# Inputs.net
KiCad netlist of a schematic drawn in Altium Designer
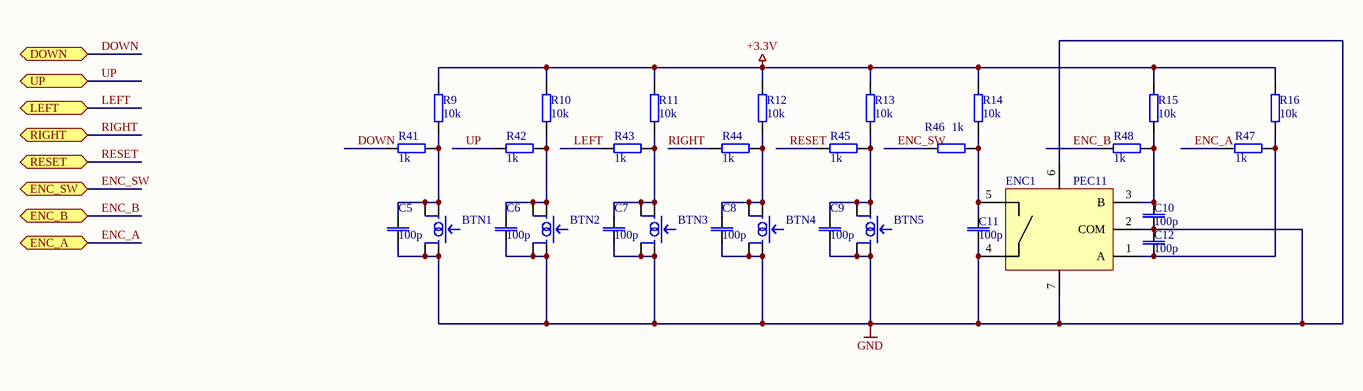
[diagram p0: Inputs.SchDoc]

(export (version "E")
  (design (tool "Eeschema 10.0.6"))
  (components
    (comp (ref "BTN1")
      (value "~")
      (footprint "PBUTTON_SMD")
      (description "Tactile push button")
      (libsource (lib "SCH_LIB") (part "PUSHBUTTON"))
    )
    (comp (ref "BTN2")
      (value "~")
      (footprint "PBUTTON_SMD")
      (description "Tactile push button")
      (libsource (lib "SCH_LIB") (part "PUSHBUTTON"))
    )
    (comp (ref "BTN3")
      (value "~")
      (footprint "PBUTTON_SMD")
      (description "Tactile push button")
      (libsource (lib "SCH_LIB") (part "PUSHBUTTON"))
    )
    (comp (ref "BTN4")
      (value "~")
      (footprint "PBUTTON_SMD")
      (description "Tactile push button")
      (libsource (lib "SCH_LIB") (part "PUSHBUTTON"))
    )
    (comp (ref "BTN5")
      (value "~")
      (footprint "PBUTTON_SMD")
      (description "Tactile push button")
      (libsource (lib "SCH_LIB") (part "PUSHBUTTON"))
    )
    (comp (ref "C5")
      (value "100p")
      (footprint "CAP 0805")
      (description "NON POLARIZED CAPACITOR")
      (libsource (lib "SCH_LIB") (part "CAP"))
    )
    (comp (ref "C6")
      (value "100p")
      (footprint "CAP 0805")
      (description "NON POLARIZED CAPACITOR")
      (libsource (lib "SCH_LIB") (part "CAP"))
    )
    (comp (ref "C7")
      (value "100p")
      (footprint "CAP 0805")
      (description "NON POLARIZED CAPACITOR")
      (libsource (lib "SCH_LIB") (part "CAP"))
    )
    (comp (ref "C8")
      (value "100p")
      (footprint "CAP 0805")
      (description "NON POLARIZED CAPACITOR")
      (libsource (lib "SCH_LIB") (part "CAP"))
    )
    (comp (ref "C9")
      (value "100p")
      (footprint "CAP 0805")
      (description "NON POLARIZED CAPACITOR")
      (libsource (lib "SCH_LIB") (part "CAP"))
    )
    (comp (ref "C10")
      (value "100p")
      (footprint "CAP 0805")
      (description "NON POLARIZED CAPACITOR")
      (libsource (lib "SCH_LIB") (part "CAP"))
    )
    (comp (ref "C11")
      (value "100p")
      (footprint "CAP 0805")
      (description "NON POLARIZED CAPACITOR")
      (libsource (lib "SCH_LIB") (part "CAP"))
    )
    (comp (ref "C12")
      (value "100p")
      (footprint "CAP 0805")
      (description "NON POLARIZED CAPACITOR")
      (libsource (lib "SCH_LIB") (part "CAP"))
    )
    (comp (ref "ENC1")
      (value "PEC11")
      (footprint "PEC11")
      (description "Mechanical rotary encoder with pushbutton")
      (libsource (lib "SCH_LIB") (part "PEC11"))
    )
    (comp (ref "R9")
      (value "10k")
      (footprint "RES 0805")
      (description "RESISTOR")
      (libsource (lib "") (part "RES_1"))
    )
    (comp (ref "R10")
      (value "10k")
      (footprint "RES 0805")
      (description "RESISTOR")
      (libsource (lib "") (part "RES_1"))
    )
    (comp (ref "R11")
      (value "10k")
      (footprint "RES 0805")
      (description "RESISTOR")
      (libsource (lib "") (part "RES_1"))
    )
    (comp (ref "R12")
      (value "10k")
      (footprint "RES 0805")
      (description "RESISTOR")
      (libsource (lib "") (part "RES_1"))
    )
    (comp (ref "R13")
      (value "10k")
      (footprint "RES 0805")
      (description "RESISTOR")
      (libsource (lib "") (part "RES_1"))
    )
    (comp (ref "R14")
      (value "10k")
      (footprint "RES 0805")
      (description "RESISTOR")
      (libsource (lib "") (part "RES_1"))
    )
    (comp (ref "R15")
      (value "10k")
      (footprint "RES 0805")
      (description "RESISTOR")
      (libsource (lib "") (part "RES_1"))
    )
    (comp (ref "R16")
      (value "10k")
      (footprint "RES 0805")
      (description "RESISTOR")
      (libsource (lib "") (part "RES_1"))
    )
    (comp (ref "R41")
      (value "1k")
      (footprint "RES 0805")
      (description "RESISTOR")
      (libsource (lib "SCH_LIB") (part "RES"))
    )
    (comp (ref "R42")
      (value "1k")
      (footprint "RES 0805")
      (description "RESISTOR")
      (libsource (lib "SCH_LIB") (part "RES"))
    )
    (comp (ref "R43")
      (value "1k")
      (footprint "RES 0805")
      (description "RESISTOR")
      (libsource (lib "SCH_LIB") (part "RES"))
    )
    (comp (ref "R44")
      (value "1k")
      (footprint "RES 0805")
      (description "RESISTOR")
      (libsource (lib "SCH_LIB") (part "RES"))
    )
    (comp (ref "R45")
      (value "1k")
      (footprint "RES 0805")
      (description "RESISTOR")
      (libsource (lib "SCH_LIB") (part "RES"))
    )
    (comp (ref "R46")
      (value "1k")
      (footprint "RES 0805")
      (description "RESISTOR")
      (libsource (lib "SCH_LIB") (part "RES"))
    )
    (comp (ref "R47")
      (value "1k")
      (footprint "RES 0805")
      (description "RESISTOR")
      (libsource (lib "SCH_LIB") (part "RES"))
    )
    (comp (ref "R48")
      (value "1k")
      (footprint "RES 0805")
      (description "RESISTOR")
      (libsource (lib "SCH_LIB") (part "RES"))
    )
  )
  (nets
    (net (code "1") (name "+3.3V") (class "Default")
      (node (ref "R10") (pin "2") (pinfunction "2_2") (pintype "passive"))
      (node (ref "R11") (pin "2") (pinfunction "2_2") (pintype "passive"))
      (node (ref "R12") (pin "2") (pinfunction "2_2") (pintype "passive"))
      (node (ref "R13") (pin "2") (pinfunction "2_2") (pintype "passive"))
      (node (ref "R14") (pin "2") (pinfunction "2_2") (pintype "passive"))
      (node (ref "R15") (pin "2") (pinfunction "2_2") (pintype "passive"))
      (node (ref "R16") (pin "2") (pinfunction "2_2") (pintype "passive"))
      (node (ref "R9") (pin "2") (pinfunction "2_2") (pintype "passive"))
    )
    (net (code "2") (name "/DOWN") (class "Default")
      (node (ref "R41") (pin "1") (pinfunction "1_1") (pintype "passive"))
    )
    (net (code "3") (name "/ENC_A") (class "Default")
      (node (ref "R47") (pin "1") (pinfunction "1_1") (pintype "passive"))
    )
    (net (code "4") (name "/ENC_B") (class "Default")
      (node (ref "R48") (pin "1") (pinfunction "1_1") (pintype "passive"))
    )
    (net (code "5") (name "/ENC_SW") (class "Default")
      (node (ref "R46") (pin "1") (pinfunction "1_1") (pintype "passive"))
    )
    (net (code "6") (name "/LEFT") (class "Default")
      (node (ref "R43") (pin "1") (pinfunction "1_1") (pintype "passive"))
    )
    (net (code "7") (name "/RESET") (class "Default")
      (node (ref "R45") (pin "1") (pinfunction "1_1") (pintype "passive"))
    )
    (net (code "8") (name "/RIGHT") (class "Default")
      (node (ref "R44") (pin "1") (pinfunction "1_1") (pintype "passive"))
    )
    (net (code "9") (name "/UP") (class "Default")
      (node (ref "R42") (pin "1") (pinfunction "1_1") (pintype "passive"))
    )
    (net (code "10") (name "GND") (class "Default")
      (node (ref "BTN1") (pin "1") (pinfunction "1_1") (pintype "passive"))
      (node (ref "BTN1") (pin "2") (pinfunction "2_2") (pintype "passive"))
      (node (ref "BTN2") (pin "1") (pinfunction "1_1") (pintype "passive"))
      (node (ref "BTN2") (pin "2") (pinfunction "2_2") (pintype "passive"))
      (node (ref "BTN3") (pin "1") (pinfunction "1_1") (pintype "passive"))
      (node (ref "BTN3") (pin "2") (pinfunction "2_2") (pintype "passive"))
      (node (ref "BTN4") (pin "1") (pinfunction "1_1") (pintype "passive"))
      (node (ref "BTN4") (pin "2") (pinfunction "2_2") (pintype "passive"))
      (node (ref "BTN5") (pin "1") (pinfunction "1_1") (pintype "passive"))
      (node (ref "BTN5") (pin "2") (pinfunction "2_2") (pintype "passive"))
      (node (ref "C10") (pin "1") (pinfunction "1_1") (pintype "passive"))
      (node (ref "C11") (pin "1") (pinfunction "1_1") (pintype "passive"))
      (node (ref "C12") (pin "2") (pinfunction "2_2") (pintype "passive"))
      (node (ref "C5") (pin "1") (pinfunction "1_1") (pintype "passive"))
      (node (ref "C6") (pin "1") (pinfunction "1_1") (pintype "passive"))
      (node (ref "C7") (pin "1") (pinfunction "1_1") (pintype "passive"))
      (node (ref "C8") (pin "1") (pinfunction "1_1") (pintype "passive"))
      (node (ref "C9") (pin "1") (pinfunction "1_1") (pintype "passive"))
      (node (ref "ENC1") (pin "2") (pinfunction "COM_2") (pintype "passive"))
      (node (ref "ENC1") (pin "4") (pinfunction "4_4") (pintype "passive"))
      (node (ref "ENC1") (pin "6") (pintype "passive"))
      (node (ref "ENC1") (pin "7") (pintype "passive"))
    )
    (net (code "11") (name "Net-(BTN1-Pad3)") (class "Default")
      (node (ref "BTN1") (pin "3") (pinfunction "3_3") (pintype "passive"))
      (node (ref "BTN1") (pin "4") (pinfunction "4_4") (pintype "passive"))
      (node (ref "C5") (pin "2") (pinfunction "2_2") (pintype "passive"))
      (node (ref "R41") (pin "2") (pinfunction "2_2") (pintype "passive"))
      (node (ref "R9") (pin "1") (pinfunction "1_1") (pintype "passive"))
    )
    (net (code "12") (name "Net-(BTN2-Pad3)") (class "Default")
      (node (ref "BTN2") (pin "3") (pinfunction "3_3") (pintype "passive"))
      (node (ref "BTN2") (pin "4") (pinfunction "4_4") (pintype "passive"))
      (node (ref "C6") (pin "2") (pinfunction "2_2") (pintype "passive"))
      (node (ref "R10") (pin "1") (pinfunction "1_1") (pintype "passive"))
      (node (ref "R42") (pin "2") (pinfunction "2_2") (pintype "passive"))
    )
    (net (code "13") (name "Net-(BTN3-Pad3)") (class "Default")
      (node (ref "BTN3") (pin "3") (pinfunction "3_3") (pintype "passive"))
      (node (ref "BTN3") (pin "4") (pinfunction "4_4") (pintype "passive"))
      (node (ref "C7") (pin "2") (pinfunction "2_2") (pintype "passive"))
      (node (ref "R11") (pin "1") (pinfunction "1_1") (pintype "passive"))
      (node (ref "R43") (pin "2") (pinfunction "2_2") (pintype "passive"))
    )
    (net (code "14") (name "Net-(BTN4-Pad3)") (class "Default")
      (node (ref "BTN4") (pin "3") (pinfunction "3_3") (pintype "passive"))
      (node (ref "BTN4") (pin "4") (pinfunction "4_4") (pintype "passive"))
      (node (ref "C8") (pin "2") (pinfunction "2_2") (pintype "passive"))
      (node (ref "R12") (pin "1") (pinfunction "1_1") (pintype "passive"))
      (node (ref "R44") (pin "2") (pinfunction "2_2") (pintype "passive"))
    )
    (net (code "15") (name "Net-(BTN5-Pad3)") (class "Default")
      (node (ref "BTN5") (pin "3") (pinfunction "3_3") (pintype "passive"))
      (node (ref "BTN5") (pin "4") (pinfunction "4_4") (pintype "passive"))
      (node (ref "C9") (pin "2") (pinfunction "2_2") (pintype "passive"))
      (node (ref "R13") (pin "1") (pinfunction "1_1") (pintype "passive"))
      (node (ref "R45") (pin "2") (pinfunction "2_2") (pintype "passive"))
    )
    (net (code "16") (name "Net-(C11-Pad2)") (class "Default")
      (node (ref "C11") (pin "2") (pinfunction "2_2") (pintype "passive"))
      (node (ref "ENC1") (pin "5") (pinfunction "5_5") (pintype "passive"))
      (node (ref "R14") (pin "1") (pinfunction "1_1") (pintype "passive"))
      (node (ref "R46") (pin "2") (pinfunction "2_2") (pintype "passive"))
    )
    (net (code "17") (name "Net-(ENC1-A)") (class "Default")
      (node (ref "C12") (pin "1") (pinfunction "1_1") (pintype "passive"))
      (node (ref "ENC1") (pin "1") (pinfunction "A_1") (pintype "passive"))
      (node (ref "R16") (pin "1") (pinfunction "1_1") (pintype "passive"))
      (node (ref "R47") (pin "2") (pinfunction "2_2") (pintype "passive"))
    )
    (net (code "18") (name "Net-(ENC1-B)") (class "Default")
      (node (ref "C10") (pin "2") (pinfunction "2_2") (pintype "passive"))
      (node (ref "ENC1") (pin "3") (pinfunction "B_3") (pintype "passive"))
      (node (ref "R15") (pin "1") (pinfunction "1_1") (pintype "passive"))
      (node (ref "R48") (pin "2") (pinfunction "2_2") (pintype "passive"))
    )
  )
)
